# Sheet3.net
KiCad netlist of a schematic drawn in Altium Designer
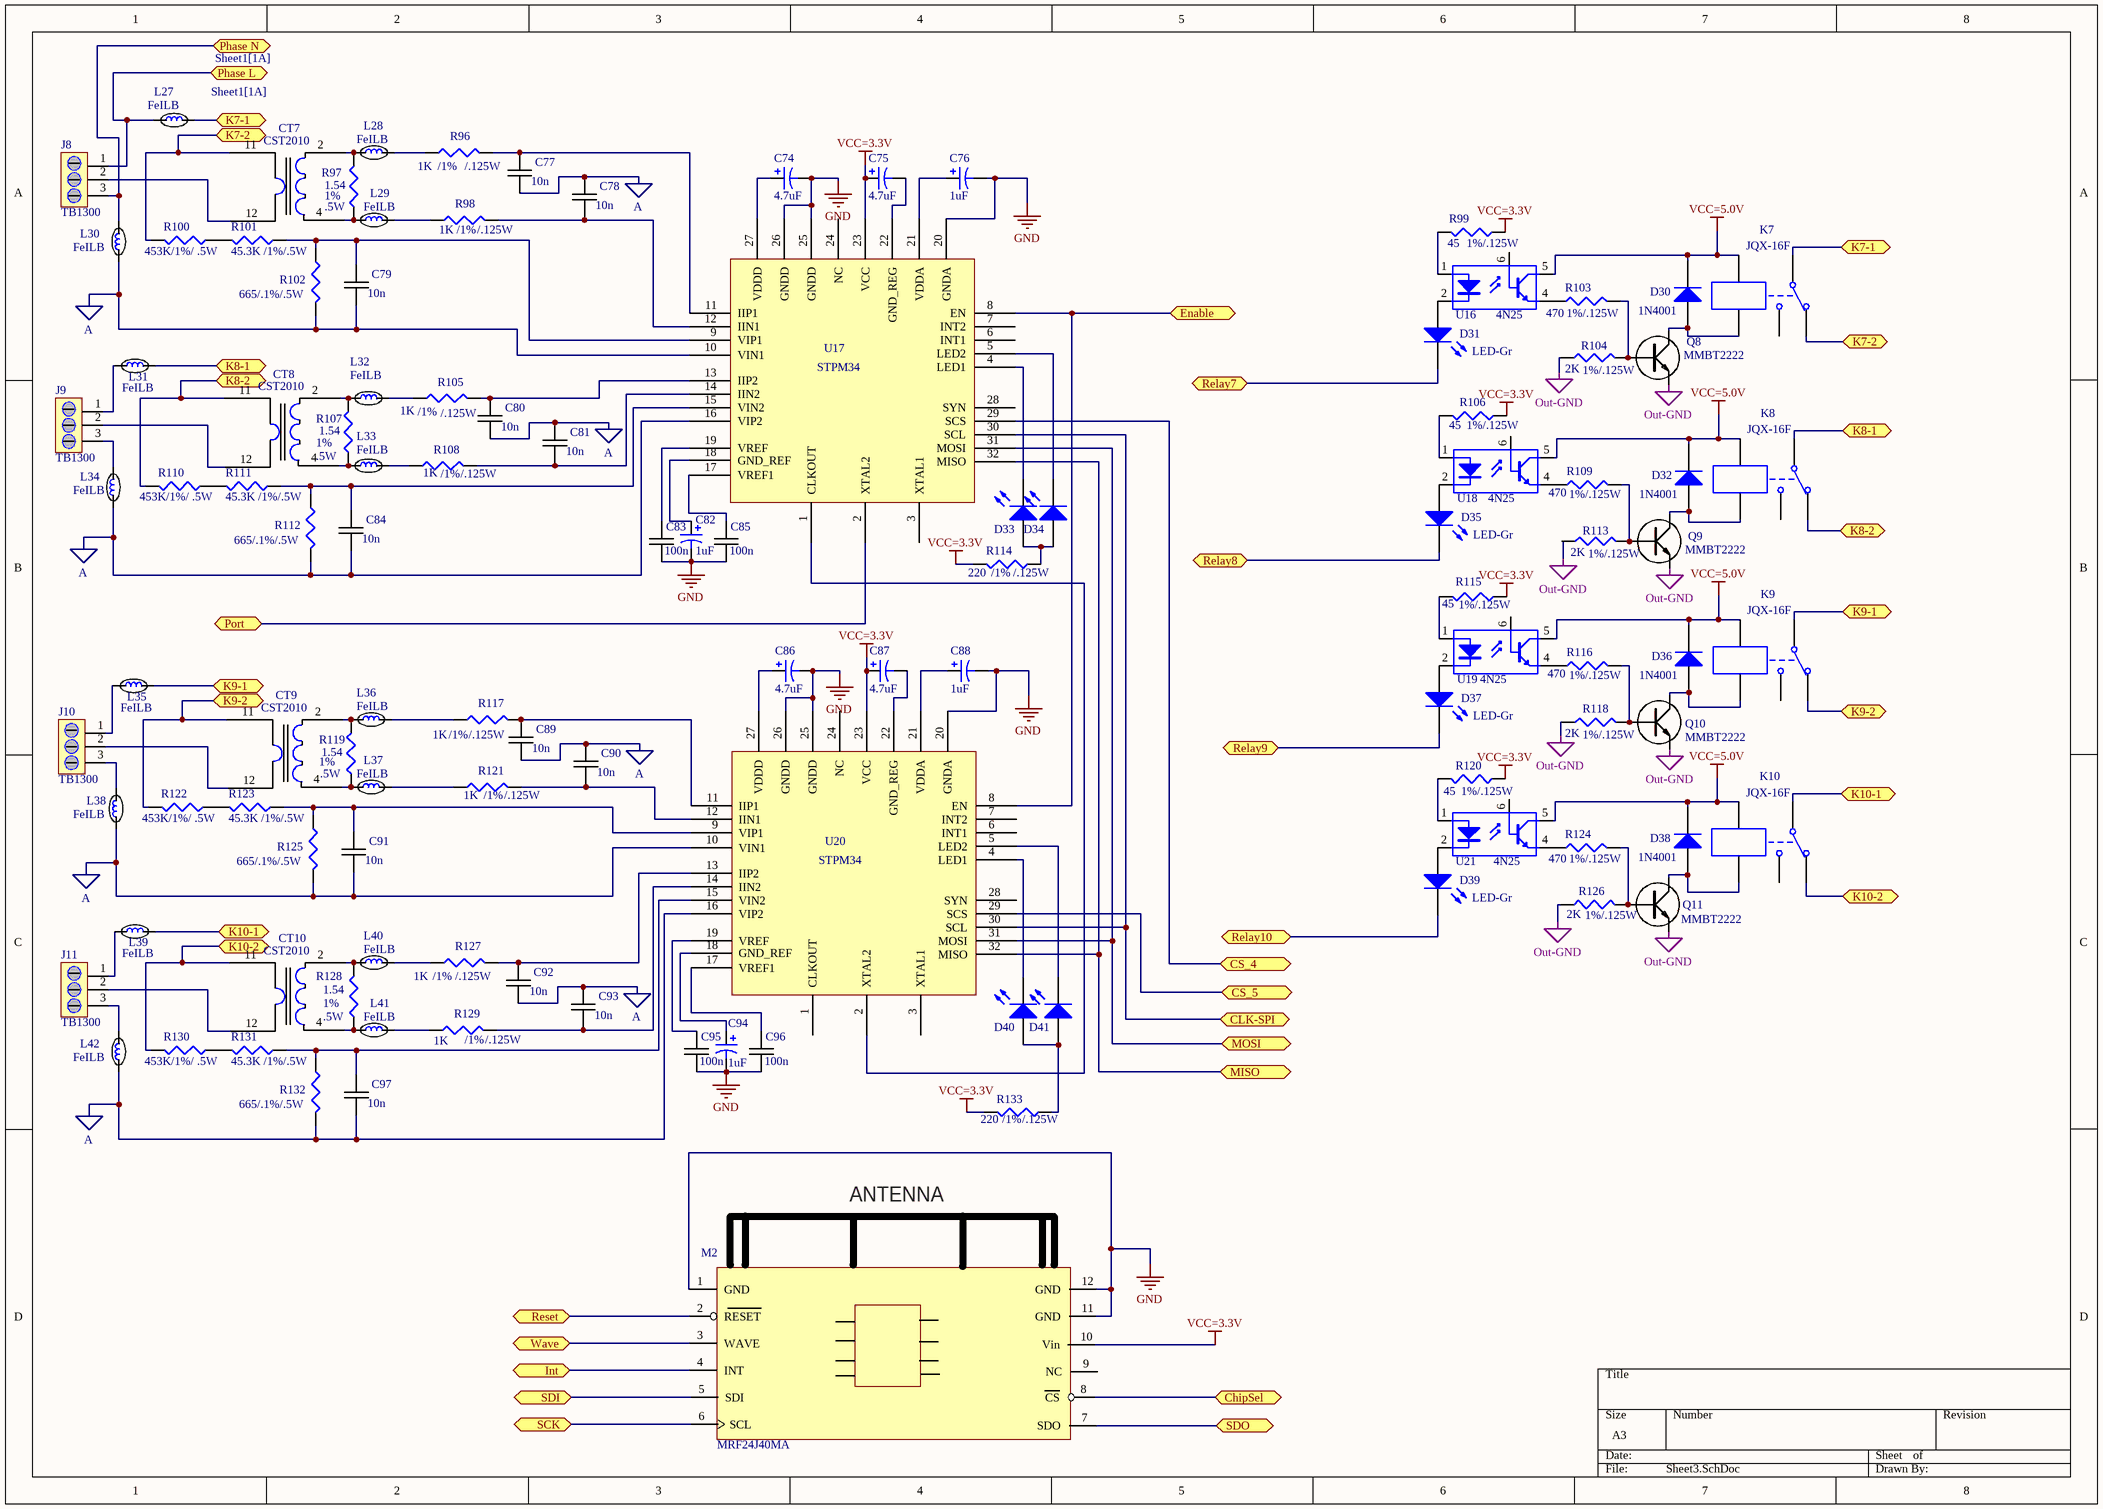
[diagram p0: Sheet3.SchDoc]

(export (version "E")
  (design (tool "Eeschema 10.0.6"))
  (components
    (comp (ref "C74")
      (value "4.7uF")
      (footprint "C0805")
      (description "Polarized Capacitor (Surface Mount)")
      (fields (field (name "MANUFACTURER") "Kemet") (field (name "PUBLISHER") "Altium Limited"))
      (libsource (lib "Miscellaneous Devices") (part "Cap Pol3"))
    )
    (comp (ref "C75")
      (value "4.7uF")
      (footprint "C0805")
      (description "Polarized Capacitor (Surface Mount)")
      (fields (field (name "MANUFACTURER") "Kemet") (field (name "PUBLISHER") "Altium Limited"))
      (libsource (lib "Miscellaneous Devices") (part "Cap Pol3"))
    )
    (comp (ref "C76")
      (value "1uF")
      (footprint "C0805")
      (description "Polarized Capacitor (Surface Mount)")
      (fields (field (name "PUBLISHER") "Altium Limited"))
      (libsource (lib "Miscellaneous Devices") (part "Cap Pol3"))
    )
    (comp (ref "C77")
      (value "10n")
      (footprint "0805C-TBD")
      (description "CAPACITOR 0805 CERAMIC")
      (fields (field (name "MANUFACTURER") "Murata Electronics"))
      (libsource (lib "vh_altium_library") (part "0805C-18PF-50V-C0G-JOH"))
    )
    (comp (ref "C78")
      (value "10n")
      (footprint "0805C-TBD")
      (description "CAPACITOR 0805 CERAMIC")
      (fields (field (name "MANUFACTURER") "Murata Electronics"))
      (libsource (lib "vh_altium_library") (part "0805C-18PF-50V-C0G-JOH"))
    )
    (comp (ref "C79")
      (value "10n")
      (footprint "0805C-TBD")
      (description "CAPACITOR 0805 CERAMIC")
      (fields (field (name "MANUFACTURER") "Murata Electronics"))
      (libsource (lib "vh_altium_library") (part "0805C-18PF-50V-C0G-JOH"))
    )
    (comp (ref "C80")
      (value "10n")
      (footprint "0805C-TBD")
      (description "CAPACITOR 0805 CERAMIC")
      (fields (field (name "MANUFACTURER") "Murata Electronics"))
      (libsource (lib "vh_altium_library") (part "0805C-18PF-50V-C0G-JOH"))
    )
    (comp (ref "C81")
      (value "10n")
      (footprint "0805C-TBD")
      (description "CAPACITOR 0805 CERAMIC")
      (fields (field (name "MANUFACTURER") "Murata Electronics"))
      (libsource (lib "vh_altium_library") (part "0805C-18PF-50V-C0G-JOH"))
    )
    (comp (ref "C82")
      (value "1uF")
      (footprint "C0805")
      (description "Polarized Capacitor (Surface Mount)")
      (fields (field (name "PUBLISHER") "Altium Limited"))
      (libsource (lib "Miscellaneous Devices") (part "Cap Pol3"))
    )
    (comp (ref "C83")
      (value "100n")
      (footprint "0805C-TBD")
      (description "CAPACITOR 0805 CERAMIC")
      (fields (field (name "MANUFACTURER") "Murata Electronnics"))
      (libsource (lib "vh_altium_library") (part "0805C-18PF-50V-C0G-JOH"))
    )
    (comp (ref "C84")
      (value "10n")
      (footprint "0805C-TBD")
      (description "CAPACITOR 0805 CERAMIC")
      (fields (field (name "MANUFACTURER") "Murata Electronics"))
      (libsource (lib "vh_altium_library") (part "0805C-18PF-50V-C0G-JOH"))
    )
    (comp (ref "C85")
      (value "100n")
      (footprint "0805C-TBD")
      (description "CAPACITOR 0805 CERAMIC")
      (fields (field (name "MANUFACTURER") "Murata Electronnics"))
      (libsource (lib "vh_altium_library") (part "0805C-18PF-50V-C0G-JOH"))
    )
    (comp (ref "C86")
      (value "4.7uF")
      (footprint "C0805")
      (description "Polarized Capacitor (Surface Mount)")
      (fields (field (name "MANUFACTURER") "Kemet") (field (name "PUBLISHER") "Altium Limited"))
      (libsource (lib "Miscellaneous Devices") (part "Cap Pol3"))
    )
    (comp (ref "C87")
      (value "4.7uF")
      (footprint "C0805")
      (description "Polarized Capacitor (Surface Mount)")
      (fields (field (name "MANUFACTURER") "Kemet") (field (name "PUBLISHER") "Altium Limited"))
      (libsource (lib "Miscellaneous Devices") (part "Cap Pol3"))
    )
    (comp (ref "C88")
      (value "1uF")
      (footprint "C0805")
      (description "Polarized Capacitor (Surface Mount)")
      (fields (field (name "PUBLISHER") "Altium Limited"))
      (libsource (lib "Miscellaneous Devices") (part "Cap Pol3"))
    )
    (comp (ref "C89")
      (value "10n")
      (footprint "0805C-TBD")
      (description "CAPACITOR 0805 CERAMIC")
      (fields (field (name "MANUFACTURER") "Murata Electronics"))
      (libsource (lib "vh_altium_library") (part "0805C-18PF-50V-C0G-JOH"))
    )
    (comp (ref "C90")
      (value "10n")
      (footprint "0805C-TBD")
      (description "CAPACITOR 0805 CERAMIC")
      (fields (field (name "MANUFACTURER") "Murata Electronics"))
      (libsource (lib "vh_altium_library") (part "0805C-18PF-50V-C0G-JOH"))
    )
    (comp (ref "C91")
      (value "10n")
      (footprint "0805C-TBD")
      (description "CAPACITOR 0805 CERAMIC")
      (fields (field (name "MANUFACTURER") "Murata Electronics"))
      (libsource (lib "vh_altium_library") (part "0805C-18PF-50V-C0G-JOH"))
    )
    (comp (ref "C92")
      (value "10n")
      (footprint "0805C-TBD")
      (description "CAPACITOR 0805 CERAMIC")
      (fields (field (name "MANUFACTURER") "Murata Electronics"))
      (libsource (lib "vh_altium_library") (part "0805C-18PF-50V-C0G-JOH"))
    )
    (comp (ref "C93")
      (value "10n")
      (footprint "0805C-TBD")
      (description "CAPACITOR 0805 CERAMIC")
      (fields (field (name "MANUFACTURER") "Murata Electronics"))
      (libsource (lib "vh_altium_library") (part "0805C-18PF-50V-C0G-JOH"))
    )
    (comp (ref "C94")
      (value "1uF")
      (footprint "C0805")
      (description "Polarized Capacitor (Surface Mount)")
      (fields (field (name "PUBLISHER") "Altium Limited"))
      (libsource (lib "Miscellaneous Devices") (part "Cap Pol3"))
    )
    (comp (ref "C95")
      (value "100n")
      (footprint "0805C-TBD")
      (description "CAPACITOR 0805 CERAMIC")
      (fields (field (name "MANUFACTURER") "Murata Electronnics"))
      (libsource (lib "vh_altium_library") (part "0805C-18PF-50V-C0G-JOH"))
    )
    (comp (ref "C96")
      (value "100n")
      (footprint "0805C-TBD")
      (description "CAPACITOR 0805 CERAMIC")
      (fields (field (name "MANUFACTURER") "Murata Electronnics"))
      (libsource (lib "vh_altium_library") (part "0805C-18PF-50V-C0G-JOH"))
    )
    (comp (ref "C97")
      (value "10n")
      (footprint "0805C-TBD")
      (description "CAPACITOR 0805 CERAMIC")
      (fields (field (name "MANUFACTURER") "Murata Electronics"))
      (libsource (lib "vh_altium_library") (part "0805C-18PF-50V-C0G-JOH"))
    )
    (comp (ref "CT7")
      (value "CST2010")
      (footprint "PcbLib3:CST2010")
      (fields (field (name "MANUFACTURER") "Coilcraft"))
      (libsource (lib "SMLib") (part "CurrentTransf"))
    )
    (comp (ref "CT8")
      (value "CST2010")
      (footprint "PcbLib3:CST2010")
      (fields (field (name "MANUFACTURER") "Coilcraft"))
      (libsource (lib "SMLib") (part "CurrentTransf"))
    )
    (comp (ref "CT9")
      (value "CST2010")
      (footprint "PcbLib3:CST2010")
      (fields (field (name "MANUFACTURER") "Coilcraft"))
      (libsource (lib "SMLib") (part "CurrentTransf"))
    )
    (comp (ref "CT10")
      (value "CST2010")
      (footprint "PcbLib3:CST2010")
      (fields (field (name "MANUFACTURER") "Coilcraft"))
      (libsource (lib "SMLib") (part "CurrentTransf"))
    )
    (comp (ref "D30")
      (value "1N4001")
      (footprint "PcbLib3:DO-214AC")
      (description "1 Amp General Purpose Rectifier")
      (fields (field (name "MANUFACTURER") "Diode Incorporated") (field (name "PUBLISHER") "Altium Limited"))
      (libsource (lib "Miscellaneous Devices") (part "Diode 1N4001"))
    )
    (comp (ref "D31")
      (value "LED-Gr")
      (footprint "3.2X1.6X1.1")
      (description "Typical RED, GREEN, YELLOW, AMBER GaAs LED")
      (fields (field (name "MANUFACTURER") "Lite-On Inc") (field (name "PUBLISHER") "Altium Limited"))
      (libsource (lib "Miscellaneous Devices") (part "LED2"))
    )
    (comp (ref "D32")
      (value "1N4001")
      (footprint "PcbLib3:DO-214AC")
      (description "1 Amp General Purpose Rectifier")
      (fields (field (name "MANUFACTURER") "Diode Incorporated") (field (name "PUBLISHER") "Altium Limited"))
      (libsource (lib "Miscellaneous Devices") (part "Diode 1N4001"))
    )
    (comp (ref "D33")
      (value "LED2")
      (footprint "3.2X1.6X1.1")
      (description "Typical RED, GREEN, YELLOW, AMBER GaAs LED")
      (fields (field (name "MANUFACTURER") "Lite-On Inc") (field (name "PUBLISHER") "Altium Limited"))
      (libsource (lib "Miscellaneous Devices") (part "LED2"))
    )
    (comp (ref "D34")
      (value "LED2")
      (footprint "3.2X1.6X1.1")
      (description "Typical RED, GREEN, YELLOW, AMBER GaAs LED")
      (fields (field (name "MANUFACTURER") "Lite-On Inc") (field (name "PUBLISHER") "Altium Limited"))
      (libsource (lib "Miscellaneous Devices") (part "LED2"))
    )
    (comp (ref "D35")
      (value "LED-Gr")
      (footprint "3.2X1.6X1.1")
      (description "Typical RED, GREEN, YELLOW, AMBER GaAs LED")
      (fields (field (name "MANUFACTURER") "Lite-On Inc") (field (name "PUBLISHER") "Altium Limited"))
      (libsource (lib "Miscellaneous Devices") (part "LED2"))
    )
    (comp (ref "D36")
      (value "1N4001")
      (footprint "PcbLib3:DO-214AC")
      (description "1 Amp General Purpose Rectifier")
      (fields (field (name "MANUFACTURER") "Diode Incorporated") (field (name "PUBLISHER") "Altium Limited"))
      (libsource (lib "Miscellaneous Devices") (part "Diode 1N4001"))
    )
    (comp (ref "D37")
      (value "LED-Gr")
      (footprint "3.2X1.6X1.1")
      (description "Typical RED, GREEN, YELLOW, AMBER GaAs LED")
      (fields (field (name "MANUFACTURER") "Lite-On Inc") (field (name "PUBLISHER") "Altium Limited"))
      (libsource (lib "Miscellaneous Devices") (part "LED2"))
    )
    (comp (ref "D38")
      (value "1N4001")
      (footprint "PcbLib3:DO-214AC")
      (description "1 Amp General Purpose Rectifier")
      (fields (field (name "MANUFACTURER") "Diode Incorporated") (field (name "PUBLISHER") "Altium Limited"))
      (libsource (lib "Miscellaneous Devices") (part "Diode 1N4001"))
    )
    (comp (ref "D39")
      (value "LED-Gr")
      (footprint "3.2X1.6X1.1")
      (description "Typical RED, GREEN, YELLOW, AMBER GaAs LED")
      (fields (field (name "MANUFACTURER") "Lite-On Inc") (field (name "PUBLISHER") "Altium Limited"))
      (libsource (lib "Miscellaneous Devices") (part "LED2"))
    )
    (comp (ref "D40")
      (value "LED2")
      (footprint "3.2X1.6X1.1")
      (description "Typical RED, GREEN, YELLOW, AMBER GaAs LED")
      (fields (field (name "MANUFACTURER") "Lite-On Inc") (field (name "PUBLISHER") "Altium Limited"))
      (libsource (lib "Miscellaneous Devices") (part "LED2"))
    )
    (comp (ref "D41")
      (value "LED2")
      (footprint "3.2X1.6X1.1")
      (description "Typical RED, GREEN, YELLOW, AMBER GaAs LED")
      (fields (field (name "MANUFACTURER") "Lite-On Inc") (field (name "PUBLISHER") "Altium Limited"))
      (libsource (lib "Miscellaneous Devices") (part "LED2"))
    )
    (comp (ref "J8")
      (value "TB1300")
      (footprint "PcbLib2:TB-1300-0-C")
      (fields (field (name "MANUFACTURER") "SCED Electronics Co.Ltd China"))
      (libsource (lib "SMLib") (part "TermBlock-2"))
    )
    (comp (ref "J9")
      (value "TB1300")
      (footprint "PcbLib2:TB-1300-0-C")
      (fields (field (name "MANUFACTURER") "SCED Electronics Co.Ltd China"))
      (libsource (lib "SMLib") (part "TermBlock-2"))
    )
    (comp (ref "J10")
      (value "TB1300")
      (footprint "PcbLib2:TB-1300-0-C")
      (fields (field (name "MANUFACTURER") "SCED Electronics Co.Ltd China"))
      (libsource (lib "SMLib") (part "TermBlock-2"))
    )
    (comp (ref "J11")
      (value "TB1300")
      (footprint "PcbLib2:TB-1300-0-C")
      (fields (field (name "MANUFACTURER") "SCED Electronics Co.Ltd China"))
      (libsource (lib "SMLib") (part "TermBlock-2"))
    )
    (comp (ref "K7")
      (value "JQX-16F")
      (footprint "PcbLib3:JQX-16f")
      (description "Single-Pole Dual-Throw Relay")
      (fields
        (field (name "MANUFACTURER") "YUEQING HENGWEI Electronics CO,Ltd")
        (field (name "PUBLISHER") "Altium Limited")
      )
      (libsource (lib "Miscellaneous Devices") (part "Relay-SPDT"))
    )
    (comp (ref "K8")
      (value "JQX-16F")
      (footprint "PcbLib3:JQX-16f")
      (description "Single-Pole Dual-Throw Relay")
      (fields
        (field (name "MANUFACTURER") "YUEQING HENGWEI Electronics CO,Ltd")
        (field (name "PUBLISHER") "Altium Limited")
      )
      (libsource (lib "Miscellaneous Devices") (part "Relay-SPDT"))
    )
    (comp (ref "K9")
      (value "JQX-16F")
      (footprint "PcbLib3:JQX-16f")
      (description "Single-Pole Dual-Throw Relay")
      (fields
        (field (name "MANUFACTURER") "YUEQING HENGWEI Electronics CO,Ltd")
        (field (name "PUBLISHER") "Altium Limited")
      )
      (libsource (lib "Miscellaneous Devices") (part "Relay-SPDT"))
    )
    (comp (ref "K10")
      (value "JQX-16F")
      (footprint "PcbLib3:JQX-16f")
      (description "Single-Pole Dual-Throw Relay")
      (fields
        (field (name "MANUFACTURER") "YUEQING HENGWEI Electronics CO,Ltd")
        (field (name "PUBLISHER") "Altium Limited")
      )
      (libsource (lib "Miscellaneous Devices") (part "Relay-SPDT"))
    )
    (comp (ref "L27")
      (value "FeILB")
      (fields (field (name "MANUFACTURER") "Brand Samsung"))
      (libsource (lib "") (part "FerrBeads/ILBB_1"))
    )
    (comp (ref "L28")
      (value "FeILB")
      (fields (field (name "MANUFACTURER") "Brand Samsung"))
      (libsource (lib "") (part "FerrBeads/ILBB_1"))
    )
    (comp (ref "L29")
      (value "FeILB")
      (fields (field (name "MANUFACTURER") "Brand Samsung"))
      (libsource (lib "") (part "FerrBeads/ILBB_1"))
    )
    (comp (ref "L30")
      (value "FeILB")
      (fields (field (name "MANUFACTURER") "Brand Samsung"))
      (libsource (lib "SMLib") (part "FerrBeads/ILBB"))
    )
    (comp (ref "L31")
      (value "FeILB")
      (fields (field (name "MANUFACTURER") "Brand Samsung"))
      (libsource (lib "") (part "FerrBeads/ILBB_1"))
    )
    (comp (ref "L32")
      (value "FeILB")
      (fields (field (name "MANUFACTURER") "Brand Samsung"))
      (libsource (lib "") (part "FerrBeads/ILBB_1"))
    )
    (comp (ref "L33")
      (value "FeILB")
      (fields (field (name "MANUFACTURER") "Brand Samsung"))
      (libsource (lib "") (part "FerrBeads/ILBB_1"))
    )
    (comp (ref "L34")
      (value "FeILB")
      (fields (field (name "MANUFACTURER") "Brand Samsung"))
      (libsource (lib "SMLib") (part "FerrBeads/ILBB"))
    )
    (comp (ref "L35")
      (value "FeILB")
      (fields (field (name "MANUFACTURER") "Brand Samsung"))
      (libsource (lib "") (part "FerrBeads/ILBB_1"))
    )
    (comp (ref "L36")
      (value "FeILB")
      (fields (field (name "MANUFACTURER") "Brand Samsung"))
      (libsource (lib "") (part "FerrBeads/ILBB_1"))
    )
    (comp (ref "L37")
      (value "FeILB")
      (fields (field (name "MANUFACTURER") "Brand Samsung"))
      (libsource (lib "") (part "FerrBeads/ILBB_1"))
    )
    (comp (ref "L38")
      (value "FeILB")
      (fields (field (name "MANUFACTURER") "Brand Samsung"))
      (libsource (lib "SMLib") (part "FerrBeads/ILBB"))
    )
    (comp (ref "L39")
      (value "FeILB")
      (fields (field (name "MANUFACTURER") "Brand Samsung"))
      (libsource (lib "") (part "FerrBeads/ILBB_1"))
    )
    (comp (ref "L40")
      (value "FeILB")
      (fields (field (name "MANUFACTURER") "Brand Samsung"))
      (libsource (lib "") (part "FerrBeads/ILBB_1"))
    )
    (comp (ref "L41")
      (value "FeILB")
      (fields (field (name "MANUFACTURER") "Brand Samsung"))
      (libsource (lib "") (part "FerrBeads/ILBB_1"))
    )
    (comp (ref "L42")
      (value "FeILB")
      (fields (field (name "MANUFACTURER") "Brand Samsung"))
      (libsource (lib "SMLib") (part "FerrBeads/ILBB"))
    )
    (comp (ref "M2")
      (value "MRF24J40MA")
      (fields (field (name "MANUFACTURER") "Microchip"))
      (libsource (lib "SMLib") (part "MRF24J40MA"))
    )
    (comp (ref "Q8")
      (value "MMBT2222")
      (footprint "SOT23-BCE")
      (description "BC847 SMALL SIGNAL NPN TRANSISTOR")
      (fields (field (name "MANUFACTURER") "Diodes  Inc."))
      (libsource (lib "vh_altium_library") (part "MMBT2222"))
    )
    (comp (ref "Q9")
      (value "MMBT2222")
      (footprint "SOT23-BCE")
      (description "BC847 SMALL SIGNAL NPN TRANSISTOR")
      (fields (field (name "MANUFACTURER") "Diodes  Inc."))
      (libsource (lib "vh_altium_library") (part "MMBT2222"))
    )
    (comp (ref "Q10")
      (value "MMBT2222")
      (footprint "SOT23-BCE")
      (description "BC847 SMALL SIGNAL NPN TRANSISTOR")
      (fields (field (name "MANUFACTURER") "Diodes  Inc."))
      (libsource (lib "vh_altium_library") (part "MMBT2222"))
    )
    (comp (ref "Q11")
      (value "MMBT2222")
      (footprint "SOT23-BCE")
      (description "BC847 SMALL SIGNAL NPN TRANSISTOR")
      (fields (field (name "MANUFACTURER") "Diodes  Inc."))
      (libsource (lib "vh_altium_library") (part "MMBT2222"))
    )
    (comp (ref "R96")
      (value "1K")
      (footprint "vh_altium_library:0805R-10")
      (description "Resistor")
      (fields
        (field (name "MANUFACTURER") "Stackpole Electronics")
        (field (name "PUBLISHER") "Altium Limited")
      )
      (libsource (lib "Miscellaneous Devices") (part "Res3"))
    )
    (comp (ref "R97")
      (value "1.54")
      (footprint "vh_altium_library:0805R-10")
      (description "Resistor")
      (fields (field (name "MANUFACTURER") "Vishay Pale") (field (name "PUBLISHER") "Altium Limited"))
      (libsource (lib "Miscellaneous Devices") (part "Res3"))
    )
    (comp (ref "R98")
      (value "1K")
      (footprint "vh_altium_library:0805R-10")
      (description "Resistor")
      (fields
        (field (name "MANUFACTURER") "Stackpole Electronics")
        (field (name "PUBLISHER") "Altium Limited")
      )
      (libsource (lib "Miscellaneous Devices") (part "Res3"))
    )
    (comp (ref "R99")
      (value "45")
      (footprint "vh_altium_library:0805R-68")
      (description "Resistor")
      (fields (field (name "PUBLISHER") "Altium Limited"))
      (libsource (lib "Miscellaneous Devices") (part "Res3"))
    )
    (comp (ref "R100")
      (value "453K/1%/ .5W")
      (footprint "generic:1210R-GENERIC")
      (description "Resistor")
      (fields (field (name "MANUFACTURER") "Panasonic  Co") (field (name "PUBLISHER") "Altium Limited"))
      (libsource (lib "Miscellaneous Devices") (part "Res3"))
    )
    (comp (ref "R101")
      (value "45.3K /1%/.5W")
      (footprint "vh_altium_library:1210C-GENERIC")
      (description "Resistor")
      (fields (field (name "MANUFACTURER") "Panasonic Co") (field (name "PUBLISHER") "Altium Limited"))
      (libsource (lib "Miscellaneous Devices") (part "Res3"))
    )
    (comp (ref "R102")
      (value "665/.1%/.5W")
      (footprint "vh_altium_library:1210C-GENERIC")
      (description "Resistor")
      (fields (field (name "MANUFACTURER") "Panasonic Co") (field (name "PUBLISHER") "Altium Limited"))
      (libsource (lib "Miscellaneous Devices") (part "Res3"))
    )
    (comp (ref "R103")
      (value "470")
      (footprint "vh_altium_library:0805R-39")
      (description "Resistor")
      (fields
        (field (name "MANUFACTURER") "Stackpole electronics")
        (field (name "PUBLISHER") "Altium Limited")
      )
      (libsource (lib "Miscellaneous Devices") (part "Res3"))
    )
    (comp (ref "R104")
      (value "2K")
      (footprint "vh_altium_library:0805R-180")
      (description "Resistor")
      (fields
        (field (name "MANUFACTURER") "Stackpole Electronics")
        (field (name "PUBLISHER") "Altium Limited")
      )
      (libsource (lib "Miscellaneous Devices") (part "Res3"))
    )
    (comp (ref "R105")
      (value "1K")
      (footprint "vh_altium_library:0805R-10")
      (description "Resistor")
      (fields
        (field (name "MANUFACTURER") "Stackpole Electronics")
        (field (name "PUBLISHER") "Altium Limited")
      )
      (libsource (lib "Miscellaneous Devices") (part "Res3"))
    )
    (comp (ref "R106")
      (value "45")
      (footprint "vh_altium_library:0805R-68")
      (description "Resistor")
      (fields (field (name "PUBLISHER") "Altium Limited"))
      (libsource (lib "Miscellaneous Devices") (part "Res3"))
    )
    (comp (ref "R107")
      (value "1.54")
      (footprint "vh_altium_library:0805R-10")
      (description "Resistor")
      (fields (field (name "MANUFACTURER") "Vishay Pale") (field (name "PUBLISHER") "Altium Limited"))
      (libsource (lib "Miscellaneous Devices") (part "Res3"))
    )
    (comp (ref "R108")
      (value "1K")
      (footprint "vh_altium_library:0805R-10")
      (description "Resistor")
      (fields
        (field (name "MANUFACTURER") "Stackpole Electronics")
        (field (name "PUBLISHER") "Altium Limited")
      )
      (libsource (lib "Miscellaneous Devices") (part "Res3"))
    )
    (comp (ref "R109")
      (value "470")
      (footprint "vh_altium_library:0805R-39")
      (description "Resistor")
      (fields
        (field (name "MANUFACTURER") "Stackpole electronics")
        (field (name "PUBLISHER") "Altium Limited")
      )
      (libsource (lib "Miscellaneous Devices") (part "Res3"))
    )
    (comp (ref "R110")
      (value "453K/1%/ .5W")
      (footprint "generic:1210R-GENERIC")
      (description "Resistor")
      (fields (field (name "MANUFACTURER") "Panasonic  Co") (field (name "PUBLISHER") "Altium Limited"))
      (libsource (lib "Miscellaneous Devices") (part "Res3"))
    )
    (comp (ref "R111")
      (value "45.3K /1%/.5W")
      (footprint "vh_altium_library:1210C-GENERIC")
      (description "Resistor")
      (fields (field (name "MANUFACTURER") "Panasonic Co") (field (name "PUBLISHER") "Altium Limited"))
      (libsource (lib "Miscellaneous Devices") (part "Res3"))
    )
    (comp (ref "R112")
      (value "665/.1%/.5W")
      (footprint "vh_altium_library:1210C-GENERIC")
      (description "Resistor")
      (fields (field (name "MANUFACTURER") "Panasonic Co") (field (name "PUBLISHER") "Altium Limited"))
      (libsource (lib "Miscellaneous Devices") (part "Res3"))
    )
    (comp (ref "R113")
      (value "2K")
      (footprint "vh_altium_library:0805R-180")
      (description "Resistor")
      (fields
        (field (name "MANUFACTURER") "Stackpole Electronics")
        (field (name "PUBLISHER") "Altium Limited")
      )
      (libsource (lib "Miscellaneous Devices") (part "Res3"))
    )
    (comp (ref "R114")
      (value "220")
      (footprint "J1-0603")
      (description "Resistor")
      (fields
        (field (name "MANUFACTURER") "Stackpole Electronics")
        (field (name "PUBLISHER") "Altium Limited")
      )
      (libsource (lib "Miscellaneous Devices") (part "Res3"))
    )
    (comp (ref "R115")
      (value "45")
      (footprint "vh_altium_library:0805R-68")
      (description "Resistor")
      (fields (field (name "PUBLISHER") "Altium Limited"))
      (libsource (lib "Miscellaneous Devices") (part "Res3"))
    )
    (comp (ref "R116")
      (value "470")
      (footprint "vh_altium_library:0805R-39")
      (description "Resistor")
      (fields
        (field (name "MANUFACTURER") "Stackpole electronics")
        (field (name "PUBLISHER") "Altium Limited")
      )
      (libsource (lib "Miscellaneous Devices") (part "Res3"))
    )
    (comp (ref "R117")
      (value "1K")
      (footprint "vh_altium_library:0805R-10")
      (description "Resistor")
      (fields
        (field (name "MANUFACTURER") "Stackpole Electronics")
        (field (name "PUBLISHER") "Altium Limited")
      )
      (libsource (lib "Miscellaneous Devices") (part "Res3"))
    )
    (comp (ref "R118")
      (value "2K")
      (footprint "vh_altium_library:0805R-180")
      (description "Resistor")
      (fields
        (field (name "MANUFACTURER") "Stackpole Electronics")
        (field (name "PUBLISHER") "Altium Limited")
      )
      (libsource (lib "Miscellaneous Devices") (part "Res3"))
    )
    (comp (ref "R119")
      (value "1.54")
      (footprint "vh_altium_library:0805R-10")
      (description "Resistor")
      (fields (field (name "MANUFACTURER") "Vishay Pale") (field (name "PUBLISHER") "Altium Limited"))
      (libsource (lib "Miscellaneous Devices") (part "Res3"))
    )
    (comp (ref "R120")
      (value "45")
      (footprint "vh_altium_library:0805R-68")
      (description "Resistor")
      (fields (field (name "PUBLISHER") "Altium Limited"))
      (libsource (lib "Miscellaneous Devices") (part "Res3"))
    )
    (comp (ref "R121")
      (value "1K")
      (footprint "vh_altium_library:0805R-10")
      (description "Resistor")
      (fields
        (field (name "MANUFACTURER") "Stackpole Electronics")
        (field (name "PUBLISHER") "Altium Limited")
      )
      (libsource (lib "Miscellaneous Devices") (part "Res3"))
    )
    (comp (ref "R122")
      (value "453K/1%/ .5W")
      (footprint "generic:1210R-GENERIC")
      (description "Resistor")
      (fields (field (name "MANUFACTURER") "Panasonic  Co") (field (name "PUBLISHER") "Altium Limited"))
      (libsource (lib "Miscellaneous Devices") (part "Res3"))
    )
    (comp (ref "R123")
      (value "45.3K /1%/.5W")
      (footprint "vh_altium_library:1210C-GENERIC")
      (description "Resistor")
      (fields (field (name "MANUFACTURER") "Panasonic Co") (field (name "PUBLISHER") "Altium Limited"))
      (libsource (lib "Miscellaneous Devices") (part "Res3"))
    )
    (comp (ref "R124")
      (value "470")
      (footprint "vh_altium_library:0805R-39")
      (description "Resistor")
      (fields
        (field (name "MANUFACTURER") "Stackpole electronics")
        (field (name "PUBLISHER") "Altium Limited")
      )
      (libsource (lib "Miscellaneous Devices") (part "Res3"))
    )
    (comp (ref "R125")
      (value "665/.1%/.5W")
      (footprint "vh_altium_library:1210C-GENERIC")
      (description "Resistor")
      (fields (field (name "MANUFACTURER") "Panasonic Co") (field (name "PUBLISHER") "Altium Limited"))
      (libsource (lib "Miscellaneous Devices") (part "Res3"))
    )
    (comp (ref "R126")
      (value "2K")
      (footprint "vh_altium_library:0805R-180")
      (description "Resistor")
      (fields
        (field (name "MANUFACTURER") "Stackpole Electronics")
        (field (name "PUBLISHER") "Altium Limited")
      )
      (libsource (lib "Miscellaneous Devices") (part "Res3"))
    )
    (comp (ref "R127")
      (value "1K")
      (footprint "vh_altium_library:0805R-10")
      (description "Resistor")
      (fields
        (field (name "MANUFACTURER") "Stackpole Electronics")
        (field (name "PUBLISHER") "Altium Limited")
      )
      (libsource (lib "Miscellaneous Devices") (part "Res3"))
    )
    (comp (ref "R128")
      (value "1.54")
      (footprint "vh_altium_library:0805R-10")
      (description "Resistor")
      (fields (field (name "MANUFACTURER") "Vishay Pale") (field (name "PUBLISHER") "Altium Limited"))
      (libsource (lib "Miscellaneous Devices") (part "Res3"))
    )
    (comp (ref "R129")
      (value "1K")
      (footprint "vh_altium_library:0805R-10")
      (description "Resistor")
      (fields
        (field (name "MANUFACTURER") "Stackpole Electronics")
        (field (name "PUBLISHER") "Altium Limited")
      )
      (libsource (lib "Miscellaneous Devices") (part "Res3"))
    )
    (comp (ref "R130")
      (value "453K/1%/ .5W")
      (footprint "generic:1210R-GENERIC")
      (description "Resistor")
      (fields (field (name "MANUFACTURER") "Panasonic  Co") (field (name "PUBLISHER") "Altium Limited"))
      (libsource (lib "Miscellaneous Devices") (part "Res3"))
    )
    (comp (ref "R131")
      (value "45.3K /1%/.5W")
      (footprint "vh_altium_library:1210C-GENERIC")
      (description "Resistor")
      (fields (field (name "MANUFACTURER") "Panasonic Co") (field (name "PUBLISHER") "Altium Limited"))
      (libsource (lib "Miscellaneous Devices") (part "Res3"))
    )
    (comp (ref "R132")
      (value "665/.1%/.5W")
      (footprint "vh_altium_library:1210C-GENERIC")
      (description "Resistor")
      (fields (field (name "MANUFACTURER") "Panasonic Co") (field (name "PUBLISHER") "Altium Limited"))
      (libsource (lib "Miscellaneous Devices") (part "Res3"))
    )
    (comp (ref "R133")
      (value "220")
      (footprint "J1-0603")
      (description "Resistor")
      (fields
        (field (name "MANUFACTURER") "Stackpole Electronics")
        (field (name "PUBLISHER") "Altium Limited")
      )
      (libsource (lib "Miscellaneous Devices") (part "Res3"))
    )
    (comp (ref "U16")
      (value "4N25")
      (footprint "SM01:4N25")
      (description "5 Pin Mini Flat Pack Optocoupler")
      (fields (field (name "MANUFACTURER") "Avago Technologies") (field (name "PUBLISHER") "Altium Limited"))
      (libsource (lib "Miscellaneous Dev3") (part "Optoisolator2"))
    )
    (comp (ref "U17")
      (value "STPM34")
      (footprint "QFN32_M")
      (fields (field (name "MANUFACTURER") "STMicroelectronic"))
      (libsource (lib "SMLib") (part "STPM34"))
    )
    (comp (ref "U18")
      (value "4N25")
      (footprint "SM01:4N25")
      (description "5 Pin Mini Flat Pack Optocoupler")
      (fields (field (name "MANUFACTURER") "Avago Technologies") (field (name "PUBLISHER") "Altium Limited"))
      (libsource (lib "Miscellaneous Dev3") (part "Optoisolator2"))
    )
    (comp (ref "U19")
      (value "4N25")
      (footprint "SM01:4N25")
      (description "5 Pin Mini Flat Pack Optocoupler")
      (fields (field (name "MANUFACTURER") "Avago Technologies") (field (name "PUBLISHER") "Altium Limited"))
      (libsource (lib "Miscellaneous Dev3") (part "Optoisolator2"))
    )
    (comp (ref "U20")
      (value "STPM34")
      (footprint "QFN32_M")
      (fields (field (name "MANUFACTURER") "STMicroelectronic"))
      (libsource (lib "SMLib") (part "STPM34"))
    )
    (comp (ref "U21")
      (value "4N25")
      (footprint "SM01:4N25")
      (description "5 Pin Mini Flat Pack Optocoupler")
      (fields (field (name "MANUFACTURER") "Avago Technologies") (field (name "PUBLISHER") "Altium Limited"))
      (libsource (lib "Miscellaneous Dev3") (part "Optoisolator2"))
    )
  )
  (nets
    (net (code "1") (name "/CLK-SPI") (class "Default")
      (node (ref "U17") (pin "30") (pinfunction "SCL_30") (pintype "passive"))
      (node (ref "U20") (pin "30") (pinfunction "SCL_30") (pintype "passive"))
    )
    (net (code "2") (name "/CS_4") (class "Default")
      (node (ref "U17") (pin "29") (pinfunction "SCS_29") (pintype "passive"))
    )
    (net (code "3") (name "/CS_5") (class "Default")
      (node (ref "U20") (pin "29") (pinfunction "SCS_29") (pintype "passive"))
    )
    (net (code "4") (name "/ChipSel") (class "Default")
      (node (ref "M2") (pin "8") (pinfunction "CS_8") (pintype "passive"))
    )
    (net (code "5") (name "/Enable") (class "Default")
      (node (ref "U17") (pin "8") (pinfunction "EN_8") (pintype "passive"))
      (node (ref "U20") (pin "8") (pinfunction "EN_8") (pintype "passive"))
    )
    (net (code "6") (name "/Int") (class "Default")
      (node (ref "M2") (pin "4") (pinfunction "INT_4") (pintype "passive"))
    )
    (net (code "7") (name "/K7-1") (class "Default")
      (node (ref "K7") (pin "1") (pinfunction "1_1") (pintype "passive"))
      (node (ref "L27") (pin "2") (pinfunction "2_2") (pintype "passive"))
    )
    (net (code "8") (name "/K7-2") (class "Default")
      (node (ref "CT7") (pin "11") (pinfunction "11_11") (pintype "passive"))
      (node (ref "K7") (pin "2") (pinfunction "2_2") (pintype "passive"))
      (node (ref "R100") (pin "2") (pinfunction "2_2") (pintype "passive"))
    )
    (net (code "9") (name "/K8-1") (class "Default")
      (node (ref "K8") (pin "1") (pinfunction "1_1") (pintype "passive"))
      (node (ref "L31") (pin "2") (pinfunction "2_2") (pintype "passive"))
    )
    (net (code "10") (name "/K8-2") (class "Default")
      (node (ref "CT8") (pin "11") (pinfunction "11_11") (pintype "passive"))
      (node (ref "K8") (pin "2") (pinfunction "2_2") (pintype "passive"))
      (node (ref "R110") (pin "2") (pinfunction "2_2") (pintype "passive"))
    )
    (net (code "11") (name "/K9-1") (class "Default")
      (node (ref "K9") (pin "1") (pinfunction "1_1") (pintype "passive"))
      (node (ref "L35") (pin "2") (pinfunction "2_2") (pintype "passive"))
    )
    (net (code "12") (name "/K9-2") (class "Default")
      (node (ref "CT9") (pin "11") (pinfunction "11_11") (pintype "passive"))
      (node (ref "K9") (pin "2") (pinfunction "2_2") (pintype "passive"))
      (node (ref "R122") (pin "2") (pinfunction "2_2") (pintype "passive"))
    )
    (net (code "13") (name "/K10-1") (class "Default")
      (node (ref "K10") (pin "1") (pinfunction "1_1") (pintype "passive"))
      (node (ref "L39") (pin "2") (pinfunction "2_2") (pintype "passive"))
    )
    (net (code "14") (name "/K10-2") (class "Default")
      (node (ref "CT10") (pin "11") (pinfunction "11_11") (pintype "passive"))
      (node (ref "K10") (pin "2") (pinfunction "2_2") (pintype "passive"))
      (node (ref "R130") (pin "2") (pinfunction "2_2") (pintype "passive"))
    )
    (net (code "15") (name "/MISO") (class "Default")
      (node (ref "U17") (pin "32") (pinfunction "MISO_32") (pintype "passive"))
      (node (ref "U20") (pin "32") (pinfunction "MISO_32") (pintype "passive"))
    )
    (net (code "16") (name "/MOSI") (class "Default")
      (node (ref "U17") (pin "31") (pinfunction "MOSI_31") (pintype "passive"))
      (node (ref "U20") (pin "31") (pinfunction "MOSI_31") (pintype "passive"))
    )
    (net (code "17") (name "/Phase L") (class "Default")
      (node (ref "J8") (pin "1") (pinfunction "1_1") (pintype "passive"))
      (node (ref "L27") (pin "1") (pinfunction "1_1") (pintype "passive"))
    )
    (net (code "18") (name "/Phase N") (class "Default")
      (node (ref "J8") (pin "3") (pinfunction "3_3") (pintype "passive"))
      (node (ref "L30") (pin "2") (pinfunction "2_2") (pintype "passive"))
    )
    (net (code "19") (name "/Port") (class "Default")
      (node (ref "U17") (pin "2") (pinfunction "XTAL2_2") (pintype "passive"))
    )
    (net (code "20") (name "/Relay7") (class "Default")
      (node (ref "D31") (pin "2") (pinfunction "K_2") (pintype "passive"))
    )
    (net (code "21") (name "/Relay8") (class "Default")
      (node (ref "D35") (pin "2") (pinfunction "K_2") (pintype "passive"))
    )
    (net (code "22") (name "/Relay9") (class "Default")
      (node (ref "D37") (pin "2") (pinfunction "K_2") (pintype "passive"))
    )
    (net (code "23") (name "/Relay10") (class "Default")
      (node (ref "D39") (pin "2") (pinfunction "K_2") (pintype "passive"))
    )
    (net (code "24") (name "/Reset") (class "Default")
      (node (ref "M2") (pin "2") (pinfunction "RESET_2") (pintype "passive"))
    )
    (net (code "25") (name "/SCK") (class "Default")
      (node (ref "M2") (pin "6") (pinfunction "SCL_6") (pintype "passive"))
    )
    (net (code "26") (name "/SDI") (class "Default")
      (node (ref "M2") (pin "5") (pinfunction "SDI_5") (pintype "passive"))
    )
    (net (code "27") (name "/SDO") (class "Default")
      (node (ref "M2") (pin "7") (pinfunction "SDO_7") (pintype "passive"))
    )
    (net (code "28") (name "/Wave") (class "Default")
      (node (ref "M2") (pin "3") (pinfunction "WAVE_3") (pintype "passive"))
    )
    (net (code "29") (name "A") (class "Default")
      (node (ref "C77") (pin "1") (pintype "passive"))
      (node (ref "C78") (pin "2") (pintype "passive"))
      (node (ref "C79") (pin "1") (pintype "passive"))
      (node (ref "C80") (pin "1") (pintype "passive"))
      (node (ref "C81") (pin "2") (pintype "passive"))
      (node (ref "C84") (pin "1") (pintype "passive"))
      (node (ref "C89") (pin "1") (pintype "passive"))
      (node (ref "C90") (pin "2") (pintype "passive"))
      (node (ref "C91") (pin "1") (pintype "passive"))
      (node (ref "C92") (pin "1") (pintype "passive"))
      (node (ref "C93") (pin "2") (pintype "passive"))
      (node (ref "C97") (pin "1") (pintype "passive"))
      (node (ref "L30") (pin "1") (pinfunction "1_1") (pintype "passive"))
      (node (ref "L34") (pin "1") (pinfunction "1_1") (pintype "passive"))
      (node (ref "L38") (pin "1") (pinfunction "1_1") (pintype "passive"))
      (node (ref "L42") (pin "1") (pinfunction "1_1") (pintype "passive"))
      (node (ref "R102") (pin "2") (pinfunction "2_2") (pintype "passive"))
      (node (ref "R125") (pin "2") (pinfunction "2_2") (pintype "passive"))
      (node (ref "R132") (pin "2") (pinfunction "2_2") (pintype "passive"))
      (node (ref "U17") (pin "10") (pinfunction "VIN1_10") (pintype "passive"))
      (node (ref "U17") (pin "16") (pinfunction "VIP2_16") (pintype "passive"))
      (node (ref "U20") (pin "10") (pinfunction "VIN1_10") (pintype "passive"))
      (node (ref "U20") (pin "16") (pinfunction "VIP2_16") (pintype "passive"))
    )
    (net (code "30") (name "GND") (class "Default")
      (node (ref "C74") (pin "2") (pinfunction "2_2") (pintype "passive"))
      (node (ref "C76") (pin "2") (pinfunction "2_2") (pintype "passive"))
      (node (ref "C82") (pin "2") (pinfunction "2_2") (pintype "passive"))
      (node (ref "C83") (pin "1") (pintype "passive"))
      (node (ref "C85") (pin "1") (pintype "passive"))
      (node (ref "C86") (pin "2") (pinfunction "2_2") (pintype "passive"))
      (node (ref "C88") (pin "2") (pinfunction "2_2") (pintype "passive"))
      (node (ref "C94") (pin "2") (pinfunction "2_2") (pintype "passive"))
      (node (ref "C95") (pin "1") (pintype "passive"))
      (node (ref "C96") (pin "1") (pintype "passive"))
      (node (ref "M2") (pin "1") (pinfunction "GND_1") (pintype "passive"))
      (node (ref "M2") (pin "11") (pinfunction "GND_11") (pintype "passive"))
      (node (ref "M2") (pin "12") (pinfunction "GND_12") (pintype "passive"))
      (node (ref "U17") (pin "20") (pinfunction "GNDA_20") (pintype "passive"))
      (node (ref "U17") (pin "25") (pinfunction "GNDD_25") (pintype "passive"))
      (node (ref "U17") (pin "26") (pinfunction "GNDD_26") (pintype "passive"))
      (node (ref "U20") (pin "20") (pinfunction "GNDA_20") (pintype "passive"))
      (node (ref "U20") (pin "25") (pinfunction "GNDD_25") (pintype "passive"))
      (node (ref "U20") (pin "26") (pinfunction "GNDD_26") (pintype "passive"))
    )
    (net (code "31") (name "Net-(CT7-69)") (class "Default")
      (node (ref "CT7") (pin "4") (pinfunction "69_4") (pintype "passive"))
      (node (ref "L29") (pin "1") (pinfunction "1_1") (pintype "passive"))
      (node (ref "R97") (pin "1") (pinfunction "1_1") (pintype "passive"))
    )
    (net (code "32") (name "Net-(CT7-Pad2)") (class "Default")
      (node (ref "CT7") (pin "2") (pinfunction "2_2") (pintype "passive"))
      (node (ref "L28") (pin "1") (pinfunction "1_1") (pintype "passive"))
      (node (ref "R97") (pin "2") (pinfunction "2_2") (pintype "passive"))
    )
    (net (code "33") (name "Net-(CT7-Pad12)") (class "Default")
      (node (ref "CT7") (pin "12") (pinfunction "12_12") (pintype "passive"))
      (node (ref "J8") (pin "2") (pinfunction "2_2") (pintype "passive"))
    )
    (net (code "34") (name "Net-(CT8-69)") (class "Default")
      (node (ref "CT8") (pin "4") (pinfunction "69_4") (pintype "passive"))
      (node (ref "L33") (pin "1") (pinfunction "1_1") (pintype "passive"))
      (node (ref "R107") (pin "1") (pinfunction "1_1") (pintype "passive"))
    )
    (net (code "35") (name "Net-(CT8-Pad2)") (class "Default")
      (node (ref "CT8") (pin "2") (pinfunction "2_2") (pintype "passive"))
      (node (ref "L32") (pin "1") (pinfunction "1_1") (pintype "passive"))
      (node (ref "R107") (pin "2") (pinfunction "2_2") (pintype "passive"))
    )
    (net (code "36") (name "Net-(CT8-Pad12)") (class "Default")
      (node (ref "CT8") (pin "12") (pinfunction "12_12") (pintype "passive"))
      (node (ref "J9") (pin "2") (pinfunction "2_2") (pintype "passive"))
    )
    (net (code "37") (name "Net-(CT9-69)") (class "Default")
      (node (ref "CT9") (pin "4") (pinfunction "69_4") (pintype "passive"))
      (node (ref "L37") (pin "1") (pinfunction "1_1") (pintype "passive"))
      (node (ref "R119") (pin "1") (pinfunction "1_1") (pintype "passive"))
    )
    (net (code "38") (name "Net-(CT9-Pad2)") (class "Default")
      (node (ref "CT9") (pin "2") (pinfunction "2_2") (pintype "passive"))
      (node (ref "L36") (pin "1") (pinfunction "1_1") (pintype "passive"))
      (node (ref "R119") (pin "2") (pinfunction "2_2") (pintype "passive"))
    )
    (net (code "39") (name "Net-(CT9-Pad12)") (class "Default")
      (node (ref "CT9") (pin "12") (pinfunction "12_12") (pintype "passive"))
      (node (ref "J10") (pin "2") (pinfunction "2_2") (pintype "passive"))
    )
    (net (code "40") (name "Net-(CT10-69)") (class "Default")
      (node (ref "CT10") (pin "4") (pinfunction "69_4") (pintype "passive"))
      (node (ref "L41") (pin "1") (pinfunction "1_1") (pintype "passive"))
      (node (ref "R128") (pin "1") (pinfunction "1_1") (pintype "passive"))
    )
    (net (code "41") (name "Net-(CT10-Pad2)") (class "Default")
      (node (ref "CT10") (pin "2") (pinfunction "2_2") (pintype "passive"))
      (node (ref "L40") (pin "1") (pinfunction "1_1") (pintype "passive"))
      (node (ref "R128") (pin "2") (pinfunction "2_2") (pintype "passive"))
    )
    (net (code "42") (name "Net-(CT10-Pad12)") (class "Default")
      (node (ref "CT10") (pin "12") (pinfunction "12_12") (pintype "passive"))
      (node (ref "J11") (pin "2") (pinfunction "2_2") (pintype "passive"))
    )
    (net (code "43") (name "Net-(D30-A)") (class "Default")
      (node (ref "D30") (pin "1") (pinfunction "A_1") (pintype "passive"))
      (node (ref "K7") (pin "5") (pinfunction "5_5") (pintype "passive"))
      (node (ref "Q8") (pin "C") (pintype "passive"))
    )
    (net (code "44") (name "Net-(D31-A)") (class "Default")
      (node (ref "D31") (pin "1") (pinfunction "A_1") (pintype "passive"))
      (node (ref "U16") (pin "2") (pinfunction "K_2") (pintype "passive"))
    )
    (net (code "45") (name "Net-(D32-A)") (class "Default")
      (node (ref "D32") (pin "1") (pinfunction "A_1") (pintype "passive"))
      (node (ref "K8") (pin "5") (pinfunction "5_5") (pintype "passive"))
      (node (ref "Q9") (pin "C") (pintype "passive"))
    )
    (net (code "46") (name "Net-(D33-A)") (class "Default")
      (node (ref "D33") (pin "1") (pinfunction "A_1") (pintype "passive"))
      (node (ref "D34") (pin "1") (pinfunction "A_1") (pintype "passive"))
      (node (ref "R114") (pin "1") (pinfunction "1_1") (pintype "passive"))
    )
    (net (code "47") (name "Net-(D33-K)") (class "Default")
      (node (ref "D33") (pin "2") (pinfunction "K_2") (pintype "passive"))
      (node (ref "U17") (pin "4") (pinfunction "LED1_4") (pintype "passive"))
    )
    (net (code "48") (name "Net-(D34-K)") (class "Default")
      (node (ref "D34") (pin "2") (pinfunction "K_2") (pintype "passive"))
      (node (ref "U17") (pin "5") (pinfunction "LED2_5") (pintype "passive"))
    )
    (net (code "49") (name "Net-(D35-A)") (class "Default")
      (node (ref "D35") (pin "1") (pinfunction "A_1") (pintype "passive"))
      (node (ref "U18") (pin "2") (pinfunction "K_2") (pintype "passive"))
    )
    (net (code "50") (name "Net-(D36-A)") (class "Default")
      (node (ref "D36") (pin "1") (pinfunction "A_1") (pintype "passive"))
      (node (ref "K9") (pin "5") (pinfunction "5_5") (pintype "passive"))
      (node (ref "Q10") (pin "C") (pintype "passive"))
    )
    (net (code "51") (name "Net-(D37-A)") (class "Default")
      (node (ref "D37") (pin "1") (pinfunction "A_1") (pintype "passive"))
      (node (ref "U19") (pin "2") (pinfunction "K_2") (pintype "passive"))
    )
    (net (code "52") (name "Net-(D38-A)") (class "Default")
      (node (ref "D38") (pin "1") (pinfunction "A_1") (pintype "passive"))
      (node (ref "K10") (pin "5") (pinfunction "5_5") (pintype "passive"))
      (node (ref "Q11") (pin "C") (pintype "passive"))
    )
    (net (code "53") (name "Net-(D39-A)") (class "Default")
      (node (ref "D39") (pin "1") (pinfunction "A_1") (pintype "passive"))
      (node (ref "U21") (pin "2") (pinfunction "K_2") (pintype "passive"))
    )
    (net (code "54") (name "Net-(D40-A)") (class "Default")
      (node (ref "D40") (pin "1") (pinfunction "A_1") (pintype "passive"))
      (node (ref "D41") (pin "1") (pinfunction "A_1") (pintype "passive"))
      (node (ref "R133") (pin "1") (pinfunction "1_1") (pintype "passive"))
    )
    (net (code "55") (name "Net-(D40-K)") (class "Default")
      (node (ref "D40") (pin "2") (pinfunction "K_2") (pintype "passive"))
      (node (ref "U20") (pin "4") (pinfunction "LED1_4") (pintype "passive"))
    )
    (net (code "56") (name "Net-(D41-K)") (class "Default")
      (node (ref "D41") (pin "2") (pinfunction "K_2") (pintype "passive"))
      (node (ref "U20") (pin "5") (pinfunction "LED2_5") (pintype "passive"))
    )
    (net (code "57") (name "Net-(J9-Pad1)") (class "Default")
      (node (ref "J9") (pin "1") (pinfunction "1_1") (pintype "passive"))
      (node (ref "L31") (pin "1") (pinfunction "1_1") (pintype "passive"))
    )
    (net (code "58") (name "Net-(J9-Pad3)") (class "Default")
      (node (ref "J9") (pin "3") (pinfunction "3_3") (pintype "passive"))
      (node (ref "L34") (pin "2") (pinfunction "2_2") (pintype "passive"))
    )
    (net (code "59") (name "Net-(J10-Pad1)") (class "Default")
      (node (ref "J10") (pin "1") (pinfunction "1_1") (pintype "passive"))
      (node (ref "L35") (pin "1") (pinfunction "1_1") (pintype "passive"))
    )
    (net (code "60") (name "Net-(J10-Pad3)") (class "Default")
      (node (ref "J10") (pin "3") (pinfunction "3_3") (pintype "passive"))
      (node (ref "L38") (pin "2") (pinfunction "2_2") (pintype "passive"))
    )
    (net (code "61") (name "Net-(J11-Pad1)") (class "Default")
      (node (ref "J11") (pin "1") (pinfunction "1_1") (pintype "passive"))
      (node (ref "L39") (pin "1") (pinfunction "1_1") (pintype "passive"))
    )
    (net (code "62") (name "Net-(J11-Pad3)") (class "Default")
      (node (ref "J11") (pin "3") (pinfunction "3_3") (pintype "passive"))
      (node (ref "L42") (pin "2") (pinfunction "2_2") (pintype "passive"))
    )
    (net (code "63") (name "Net-(L28-Pad2)") (class "Default")
      (node (ref "L28") (pin "2") (pinfunction "2_2") (pintype "passive"))
      (node (ref "R96") (pin "1") (pinfunction "1_1") (pintype "passive"))
    )
    (net (code "64") (name "Net-(L29-Pad2)") (class "Default")
      (node (ref "L29") (pin "2") (pinfunction "2_2") (pintype "passive"))
      (node (ref "R98") (pin "1") (pinfunction "1_1") (pintype "passive"))
    )
    (net (code "65") (name "Net-(L32-Pad2)") (class "Default")
      (node (ref "L32") (pin "2") (pinfunction "2_2") (pintype "passive"))
      (node (ref "R105") (pin "1") (pinfunction "1_1") (pintype "passive"))
    )
    (net (code "66") (name "Net-(L33-Pad2)") (class "Default")
      (node (ref "L33") (pin "2") (pinfunction "2_2") (pintype "passive"))
      (node (ref "R108") (pin "1") (pinfunction "1_1") (pintype "passive"))
    )
    (net (code "67") (name "Net-(L36-Pad2)") (class "Default")
      (node (ref "L36") (pin "2") (pinfunction "2_2") (pintype "passive"))
      (node (ref "R117") (pin "1") (pinfunction "1_1") (pintype "passive"))
    )
    (net (code "68") (name "Net-(L37-Pad2)") (class "Default")
      (node (ref "L37") (pin "2") (pinfunction "2_2") (pintype "passive"))
      (node (ref "R121") (pin "1") (pinfunction "1_1") (pintype "passive"))
    )
    (net (code "69") (name "Net-(L40-Pad2)") (class "Default")
      (node (ref "L40") (pin "2") (pinfunction "2_2") (pintype "passive"))
      (node (ref "R127") (pin "1") (pinfunction "1_1") (pintype "passive"))
    )
    (net (code "70") (name "Net-(L41-Pad2)") (class "Default")
      (node (ref "L41") (pin "2") (pinfunction "2_2") (pintype "passive"))
      (node (ref "R129") (pin "1") (pinfunction "1_1") (pintype "passive"))
    )
    (net (code "71") (name "Net-(Q8-PadB)") (class "Default")
      (node (ref "Q8") (pin "B") (pintype "passive"))
      (node (ref "R103") (pin "2") (pinfunction "2_2") (pintype "passive"))
      (node (ref "R104") (pin "2") (pinfunction "2_2") (pintype "passive"))
    )
    (net (code "72") (name "Net-(Q9-PadB)") (class "Default")
      (node (ref "Q9") (pin "B") (pintype "passive"))
      (node (ref "R109") (pin "2") (pinfunction "2_2") (pintype "passive"))
      (node (ref "R113") (pin "2") (pinfunction "2_2") (pintype "passive"))
    )
    (net (code "73") (name "Net-(Q10-PadB)") (class "Default")
      (node (ref "Q10") (pin "B") (pintype "passive"))
      (node (ref "R116") (pin "2") (pinfunction "2_2") (pintype "passive"))
      (node (ref "R118") (pin "2") (pinfunction "2_2") (pintype "passive"))
    )
    (net (code "74") (name "Net-(Q11-PadB)") (class "Default")
      (node (ref "Q11") (pin "B") (pintype "passive"))
      (node (ref "R124") (pin "2") (pinfunction "2_2") (pintype "passive"))
      (node (ref "R126") (pin "2") (pinfunction "2_2") (pintype "passive"))
    )
    (net (code "75") (name "Net-(R100-Pad1)") (class "Default")
      (node (ref "R100") (pin "1") (pinfunction "1_1") (pintype "passive"))
      (node (ref "R101") (pin "2") (pinfunction "2_2") (pintype "passive"))
    )
    (net (code "76") (name "Net-(R110-Pad1)") (class "Default")
      (node (ref "R110") (pin "1") (pinfunction "1_1") (pintype "passive"))
      (node (ref "R111") (pin "2") (pinfunction "2_2") (pintype "passive"))
    )
    (net (code "77") (name "Net-(R122-Pad1)") (class "Default")
      (node (ref "R122") (pin "1") (pinfunction "1_1") (pintype "passive"))
      (node (ref "R123") (pin "2") (pinfunction "2_2") (pintype "passive"))
    )
    (net (code "78") (name "Net-(R130-Pad1)") (class "Default")
      (node (ref "R130") (pin "1") (pinfunction "1_1") (pintype "passive"))
      (node (ref "R131") (pin "2") (pinfunction "2_2") (pintype "passive"))
    )
    (net (code "79") (name "Net-(U16-A)") (class "Default")
      (node (ref "R99") (pin "2") (pinfunction "2_2") (pintype "passive"))
      (node (ref "U16") (pin "1") (pinfunction "A_1") (pintype "passive"))
    )
    (net (code "80") (name "Net-(U16-E)") (class "Default")
      (node (ref "R103") (pin "1") (pinfunction "1_1") (pintype "passive"))
      (node (ref "U16") (pin "4") (pinfunction "E_4") (pintype "passive"))
    )
    (net (code "81") (name "Net-(U17-CLKOUT)") (class "Default")
      (node (ref "U17") (pin "1") (pinfunction "CLKOUT_1") (pintype "passive"))
      (node (ref "U20") (pin "2") (pinfunction "XTAL2_2") (pintype "passive"))
    )
    (net (code "82") (name "Net-(U17-GND_REF)") (class "Default")
      (node (ref "C82") (pin "1") (pinfunction "1_1") (pintype "passive"))
      (node (ref "U17") (pin "18") (pinfunction "GND_REF_18") (pintype "passive"))
    )
    (net (code "83") (name "Net-(U17-GND_REG)") (class "Default")
      (node (ref "C75") (pin "2") (pinfunction "2_2") (pintype "passive"))
      (node (ref "U17") (pin "22") (pinfunction "GND_REG_22") (pintype "passive"))
    )
    (net (code "84") (name "Net-(U17-IIN1)") (class "Default")
      (node (ref "C78") (pin "1") (pintype "passive"))
      (node (ref "R98") (pin "2") (pinfunction "2_2") (pintype "passive"))
      (node (ref "U17") (pin "12") (pinfunction "IIN1_12") (pintype "passive"))
    )
    (net (code "85") (name "Net-(U17-IIN2)") (class "Default")
      (node (ref "C81") (pin "1") (pintype "passive"))
      (node (ref "R108") (pin "2") (pinfunction "2_2") (pintype "passive"))
      (node (ref "U17") (pin "14") (pinfunction "IIN2_14") (pintype "passive"))
    )
    (net (code "86") (name "Net-(U17-IIP1)") (class "Default")
      (node (ref "C77") (pin "2") (pintype "passive"))
      (node (ref "R96") (pin "2") (pinfunction "2_2") (pintype "passive"))
      (node (ref "U17") (pin "11") (pinfunction "IIP1_11") (pintype "passive"))
    )
    (net (code "87") (name "Net-(U17-IIP2)") (class "Default")
      (node (ref "C80") (pin "2") (pintype "passive"))
      (node (ref "R105") (pin "2") (pinfunction "2_2") (pintype "passive"))
      (node (ref "U17") (pin "13") (pinfunction "IIP2_13") (pintype "passive"))
    )
    (net (code "88") (name "Net-(U17-VDDA)") (class "Default")
      (node (ref "C76") (pin "1") (pinfunction "1_1") (pintype "passive"))
      (node (ref "U17") (pin "21") (pinfunction "VDDA_21") (pintype "passive"))
    )
    (net (code "89") (name "Net-(U17-VDDD)") (class "Default")
      (node (ref "C74") (pin "1") (pinfunction "1_1") (pintype "passive"))
      (node (ref "U17") (pin "27") (pinfunction "VDDD_27") (pintype "passive"))
    )
    (net (code "90") (name "Net-(U17-VIN2)") (class "Default")
      (node (ref "C84") (pin "2") (pintype "passive"))
      (node (ref "R111") (pin "1") (pinfunction "1_1") (pintype "passive"))
      (node (ref "R112") (pin "1") (pinfunction "1_1") (pintype "passive"))
      (node (ref "U17") (pin "15") (pinfunction "VIN2_15") (pintype "passive"))
    )
    (net (code "91") (name "Net-(U17-VIP1)") (class "Default")
      (node (ref "C79") (pin "2") (pintype "passive"))
      (node (ref "R101") (pin "1") (pinfunction "1_1") (pintype "passive"))
      (node (ref "R102") (pin "1") (pinfunction "1_1") (pintype "passive"))
      (node (ref "U17") (pin "9") (pinfunction "VIP1_9") (pintype "passive"))
    )
    (net (code "92") (name "Net-(U17-VREF)") (class "Default")
      (node (ref "C83") (pin "2") (pintype "passive"))
      (node (ref "U17") (pin "19") (pinfunction "VREF_19") (pintype "passive"))
    )
    (net (code "93") (name "Net-(U17-VREF1)") (class "Default")
      (node (ref "C85") (pin "2") (pintype "passive"))
      (node (ref "U17") (pin "17") (pinfunction "VREF1_17") (pintype "passive"))
    )
    (net (code "94") (name "Net-(U18-A)") (class "Default")
      (node (ref "R106") (pin "2") (pinfunction "2_2") (pintype "passive"))
      (node (ref "U18") (pin "1") (pinfunction "A_1") (pintype "passive"))
    )
    (net (code "95") (name "Net-(U18-E)") (class "Default")
      (node (ref "R109") (pin "1") (pinfunction "1_1") (pintype "passive"))
      (node (ref "U18") (pin "4") (pinfunction "E_4") (pintype "passive"))
    )
    (net (code "96") (name "Net-(U19-A)") (class "Default")
      (node (ref "R115") (pin "2") (pinfunction "2_2") (pintype "passive"))
      (node (ref "U19") (pin "1") (pinfunction "A_1") (pintype "passive"))
    )
    (net (code "97") (name "Net-(U19-E)") (class "Default")
      (node (ref "R116") (pin "1") (pinfunction "1_1") (pintype "passive"))
      (node (ref "U19") (pin "4") (pinfunction "E_4") (pintype "passive"))
    )
    (net (code "98") (name "Net-(U20-GND_REF)") (class "Default")
      (node (ref "C94") (pin "1") (pinfunction "1_1") (pintype "passive"))
      (node (ref "U20") (pin "18") (pinfunction "GND_REF_18") (pintype "passive"))
    )
    (net (code "99") (name "Net-(U20-GND_REG)") (class "Default")
      (node (ref "C87") (pin "2") (pinfunction "2_2") (pintype "passive"))
      (node (ref "U20") (pin "22") (pinfunction "GND_REG_22") (pintype "passive"))
    )
    (net (code "100") (name "Net-(U20-IIN1)") (class "Default")
      (node (ref "C90") (pin "1") (pintype "passive"))
      (node (ref "R121") (pin "2") (pinfunction "2_2") (pintype "passive"))
      (node (ref "U20") (pin "12") (pinfunction "IIN1_12") (pintype "passive"))
    )
    (net (code "101") (name "Net-(U20-IIN2)") (class "Default")
      (node (ref "C93") (pin "1") (pintype "passive"))
      (node (ref "R129") (pin "2") (pinfunction "2_2") (pintype "passive"))
      (node (ref "U20") (pin "14") (pinfunction "IIN2_14") (pintype "passive"))
    )
    (net (code "102") (name "Net-(U20-IIP1)") (class "Default")
      (node (ref "C89") (pin "2") (pintype "passive"))
      (node (ref "R117") (pin "2") (pinfunction "2_2") (pintype "passive"))
      (node (ref "U20") (pin "11") (pinfunction "IIP1_11") (pintype "passive"))
    )
    (net (code "103") (name "Net-(U20-IIP2)") (class "Default")
      (node (ref "C92") (pin "2") (pintype "passive"))
      (node (ref "R127") (pin "2") (pinfunction "2_2") (pintype "passive"))
      (node (ref "U20") (pin "13") (pinfunction "IIP2_13") (pintype "passive"))
    )
    (net (code "104") (name "Net-(U20-VDDA)") (class "Default")
      (node (ref "C88") (pin "1") (pinfunction "1_1") (pintype "passive"))
      (node (ref "U20") (pin "21") (pinfunction "VDDA_21") (pintype "passive"))
    )
    (net (code "105") (name "Net-(U20-VDDD)") (class "Default")
      (node (ref "C86") (pin "1") (pinfunction "1_1") (pintype "passive"))
      (node (ref "U20") (pin "27") (pinfunction "VDDD_27") (pintype "passive"))
    )
    (net (code "106") (name "Net-(U20-VIN2)") (class "Default")
      (node (ref "C97") (pin "2") (pintype "passive"))
      (node (ref "R131") (pin "1") (pinfunction "1_1") (pintype "passive"))
      (node (ref "R132") (pin "1") (pinfunction "1_1") (pintype "passive"))
      (node (ref "U20") (pin "15") (pinfunction "VIN2_15") (pintype "passive"))
    )
    (net (code "107") (name "Net-(U20-VIP1)") (class "Default")
      (node (ref "C91") (pin "2") (pintype "passive"))
      (node (ref "R123") (pin "1") (pinfunction "1_1") (pintype "passive"))
      (node (ref "R125") (pin "1") (pinfunction "1_1") (pintype "passive"))
      (node (ref "U20") (pin "9") (pinfunction "VIP1_9") (pintype "passive"))
    )
    (net (code "108") (name "Net-(U20-VREF)") (class "Default")
      (node (ref "C95") (pin "2") (pintype "passive"))
      (node (ref "U20") (pin "19") (pinfunction "VREF_19") (pintype "passive"))
    )
    (net (code "109") (name "Net-(U20-VREF1)") (class "Default")
      (node (ref "C96") (pin "2") (pintype "passive"))
      (node (ref "U20") (pin "17") (pinfunction "VREF1_17") (pintype "passive"))
    )
    (net (code "110") (name "Net-(U21-A)") (class "Default")
      (node (ref "R120") (pin "2") (pinfunction "2_2") (pintype "passive"))
      (node (ref "U21") (pin "1") (pinfunction "A_1") (pintype "passive"))
    )
    (net (code "111") (name "Net-(U21-E)") (class "Default")
      (node (ref "R124") (pin "1") (pinfunction "1_1") (pintype "passive"))
      (node (ref "U21") (pin "4") (pinfunction "E_4") (pintype "passive"))
    )
    (net (code "112") (name "Out-GND") (class "Default")
      (node (ref "Q10") (pin "E") (pintype "passive"))
      (node (ref "Q11") (pin "E") (pintype "passive"))
      (node (ref "Q8") (pin "E") (pintype "passive"))
      (node (ref "Q9") (pin "E") (pintype "passive"))
      (node (ref "R104") (pin "1") (pinfunction "1_1") (pintype "passive"))
      (node (ref "R113") (pin "1") (pinfunction "1_1") (pintype "passive"))
      (node (ref "R118") (pin "1") (pinfunction "1_1") (pintype "passive"))
      (node (ref "R126") (pin "1") (pinfunction "1_1") (pintype "passive"))
    )
    (net (code "113") (name "VCC=3.3V") (class "Default")
      (node (ref "C75") (pin "1") (pinfunction "1_1") (pintype "passive"))
      (node (ref "C87") (pin "1") (pinfunction "1_1") (pintype "passive"))
      (node (ref "M2") (pin "10") (pinfunction "Vin_10") (pintype "passive"))
      (node (ref "R106") (pin "1") (pinfunction "1_1") (pintype "passive"))
      (node (ref "R114") (pin "2") (pinfunction "2_2") (pintype "passive"))
      (node (ref "R115") (pin "1") (pinfunction "1_1") (pintype "passive"))
      (node (ref "R120") (pin "1") (pinfunction "1_1") (pintype "passive"))
      (node (ref "R133") (pin "2") (pinfunction "2_2") (pintype "passive"))
      (node (ref "R99") (pin "1") (pinfunction "1_1") (pintype "passive"))
      (node (ref "U17") (pin "23") (pinfunction "VCC_23") (pintype "passive"))
      (node (ref "U20") (pin "23") (pinfunction "VCC_23") (pintype "passive"))
    )
    (net (code "114") (name "VCC=5.0V") (class "Default")
      (node (ref "D30") (pin "2") (pinfunction "K_2") (pintype "passive"))
      (node (ref "D32") (pin "2") (pinfunction "K_2") (pintype "passive"))
      (node (ref "D36") (pin "2") (pinfunction "K_2") (pintype "passive"))
      (node (ref "D38") (pin "2") (pinfunction "K_2") (pintype "passive"))
      (node (ref "K10") (pin "4") (pinfunction "4_4") (pintype "passive"))
      (node (ref "K7") (pin "4") (pinfunction "4_4") (pintype "passive"))
      (node (ref "K8") (pin "4") (pinfunction "4_4") (pintype "passive"))
      (node (ref "K9") (pin "4") (pinfunction "4_4") (pintype "passive"))
      (node (ref "U16") (pin "5") (pinfunction "C_5") (pintype "passive"))
      (node (ref "U18") (pin "5") (pinfunction "C_5") (pintype "passive"))
      (node (ref "U19") (pin "5") (pinfunction "C_5") (pintype "passive"))
      (node (ref "U21") (pin "5") (pinfunction "C_5") (pintype "passive"))
    )
    (net (code "115") (name "unconnected-(K7-Pad3)") (class "Default")
      (node (ref "K7") (pin "3") (pinfunction "3_3") (pintype "passive"))
    )
    (net (code "116") (name "unconnected-(K8-Pad3)") (class "Default")
      (node (ref "K8") (pin "3") (pinfunction "3_3") (pintype "passive"))
    )
    (net (code "117") (name "unconnected-(K9-Pad3)") (class "Default")
      (node (ref "K9") (pin "3") (pinfunction "3_3") (pintype "passive"))
    )
    (net (code "118") (name "unconnected-(K10-Pad3)") (class "Default")
      (node (ref "K10") (pin "3") (pinfunction "3_3") (pintype "passive"))
    )
    (net (code "119") (name "unconnected-(M2-NC-Pad9)") (class "Default")
      (node (ref "M2") (pin "9") (pinfunction "NC_9") (pintype "passive"))
    )
    (net (code "120") (name "unconnected-(R112-Pad2)") (class "Default")
      (node (ref "R112") (pin "2") (pinfunction "2_2") (pintype "passive"))
    )
    (net (code "121") (name "unconnected-(U16-B-Pad6)") (class "Default")
      (node (ref "U16") (pin "6") (pinfunction "B_6") (pintype "passive"))
    )
    (net (code "122") (name "unconnected-(U17-INT1-Pad6)") (class "Default")
      (node (ref "U17") (pin "6") (pinfunction "INT1_6") (pintype "passive"))
    )
    (net (code "123") (name "unconnected-(U17-INT2-Pad7)") (class "Default")
      (node (ref "U17") (pin "7") (pinfunction "INT2_7") (pintype "passive"))
    )
    (net (code "124") (name "unconnected-(U17-NC-Pad24)") (class "Default")
      (node (ref "U17") (pin "24") (pinfunction "NC_24") (pintype "passive"))
    )
    (net (code "125") (name "unconnected-(U17-SYN-Pad28)") (class "Default")
      (node (ref "U17") (pin "28") (pinfunction "SYN_28") (pintype "passive"))
    )
    (net (code "126") (name "unconnected-(U17-XTAL1-Pad3)") (class "Default")
      (node (ref "U17") (pin "3") (pinfunction "XTAL1_3") (pintype "passive"))
    )
    (net (code "127") (name "unconnected-(U18-B-Pad6)") (class "Default")
      (node (ref "U18") (pin "6") (pinfunction "B_6") (pintype "passive"))
    )
    (net (code "128") (name "unconnected-(U19-B-Pad6)") (class "Default")
      (node (ref "U19") (pin "6") (pinfunction "B_6") (pintype "passive"))
    )
    (net (code "129") (name "unconnected-(U20-CLKOUT-Pad1)") (class "Default")
      (node (ref "U20") (pin "1") (pinfunction "CLKOUT_1") (pintype "passive"))
    )
    (net (code "130") (name "unconnected-(U20-INT1-Pad6)") (class "Default")
      (node (ref "U20") (pin "6") (pinfunction "INT1_6") (pintype "passive"))
    )
    (net (code "131") (name "unconnected-(U20-INT2-Pad7)") (class "Default")
      (node (ref "U20") (pin "7") (pinfunction "INT2_7") (pintype "passive"))
    )
    (net (code "132") (name "unconnected-(U20-NC-Pad24)") (class "Default")
      (node (ref "U20") (pin "24") (pinfunction "NC_24") (pintype "passive"))
    )
    (net (code "133") (name "unconnected-(U20-SYN-Pad28)") (class "Default")
      (node (ref "U20") (pin "28") (pinfunction "SYN_28") (pintype "passive"))
    )
    (net (code "134") (name "unconnected-(U20-XTAL1-Pad3)") (class "Default")
      (node (ref "U20") (pin "3") (pinfunction "XTAL1_3") (pintype "passive"))
    )
    (net (code "135") (name "unconnected-(U21-B-Pad6)") (class "Default")
      (node (ref "U21") (pin "6") (pinfunction "B_6") (pintype "passive"))
    )
  )
)
